# Superseal.net
KiCad netlist of a schematic drawn in Altium Designer
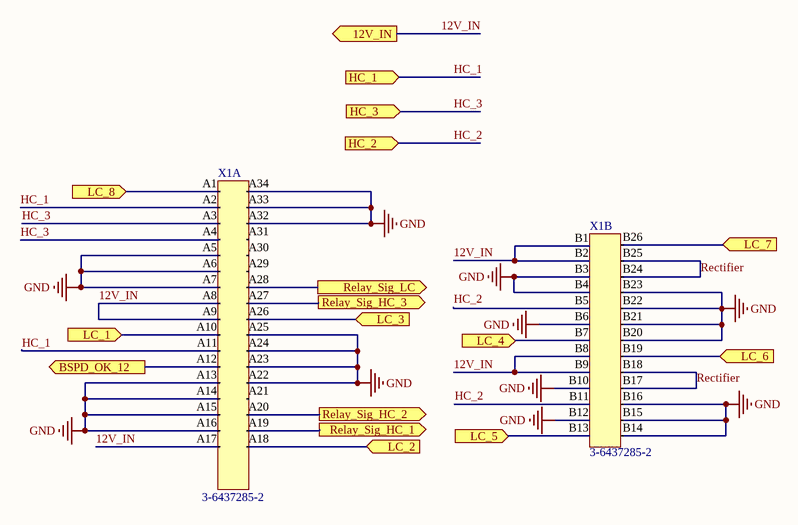
[diagram p0: Superseal.SchDoc]

(export (version "E")
  (design (tool "Eeschema 10.0.6"))
  (components
    (comp (ref "X1")
      (value "3-6437285-2")
      (footprint "SUPERSEAL 60POS 90Deg")
      (description "90 Degree")
      (libsource (lib "Altium-Lib") (part "CONN Superseal 60POS"))
    )
  )
  (nets
    (net (code "1") (name "/12V_IN") (class "Default")
      (node (ref "X1") (pin "A17") (pintype "bidirectional"))
      (node (ref "X1") (pin "A8") (pintype "bidirectional"))
      (node (ref "X1") (pin "A9") (pintype "bidirectional"))
      (node (ref "X1") (pin "B1") (pintype "bidirectional"))
      (node (ref "X1") (pin "B2") (pintype "bidirectional"))
      (node (ref "X1") (pin "B8") (pintype "bidirectional"))
      (node (ref "X1") (pin "B9") (pintype "bidirectional"))
    )
    (net (code "2") (name "/BSPD_OK_12") (class "Default")
      (node (ref "X1") (pin "A12") (pintype "bidirectional"))
    )
    (net (code "3") (name "/HC_1") (class "Default")
      (node (ref "X1") (pin "A11") (pintype "bidirectional"))
      (node (ref "X1") (pin "A2") (pintype "bidirectional"))
    )
    (net (code "4") (name "/HC_2") (class "Default")
      (node (ref "X1") (pin "B11") (pintype "bidirectional"))
      (node (ref "X1") (pin "B5") (pintype "bidirectional"))
    )
    (net (code "5") (name "/HC_3") (class "Default")
      (node (ref "X1") (pin "A3") (pintype "bidirectional"))
      (node (ref "X1") (pin "A4") (pintype "bidirectional"))
    )
    (net (code "6") (name "/LC_1") (class "Default") (node (ref "X1") (pin "A10") (pintype "bidirectional")))
    (net (code "7") (name "/LC_2") (class "Default") (node (ref "X1") (pin "A18") (pintype "bidirectional")))
    (net (code "8") (name "/LC_3") (class "Default") (node (ref "X1") (pin "A26") (pintype "bidirectional")))
    (net (code "9") (name "/LC_4") (class "Default") (node (ref "X1") (pin "B7") (pintype "bidirectional")))
    (net (code "10") (name "/LC_5") (class "Default") (node (ref "X1") (pin "B13") (pintype "bidirectional")))
    (net (code "11") (name "/LC_6") (class "Default") (node (ref "X1") (pin "B19") (pintype "bidirectional")))
    (net (code "12") (name "/LC_7") (class "Default") (node (ref "X1") (pin "B26") (pintype "bidirectional")))
    (net (code "13") (name "/LC_8") (class "Default") (node (ref "X1") (pin "A1") (pintype "bidirectional")))
    (net (code "14") (name "/Rectifier") (class "Default")
      (node (ref "X1") (pin "B17") (pintype "bidirectional"))
      (node (ref "X1") (pin "B18") (pintype "bidirectional"))
      (node (ref "X1") (pin "B24") (pintype "bidirectional"))
      (node (ref "X1") (pin "B25") (pintype "bidirectional"))
    )
    (net (code "15") (name "/Relay_Sig_HC_1") (class "Default")
      (node (ref "X1") (pin "A19") (pintype "bidirectional"))
    )
    (net (code "16") (name "/Relay_Sig_HC_2") (class "Default")
      (node (ref "X1") (pin "A20") (pintype "bidirectional"))
    )
    (net (code "17") (name "/Relay_Sig_HC_3") (class "Default")
      (node (ref "X1") (pin "A27") (pintype "bidirectional"))
    )
    (net (code "18") (name "/Relay_Sig_LC") (class "Default")
      (node (ref "X1") (pin "A28") (pintype "bidirectional"))
    )
    (net (code "19") (name "GND") (class "Default")
      (node (ref "X1") (pin "A13") (pintype "bidirectional"))
      (node (ref "X1") (pin "A14") (pintype "bidirectional"))
      (node (ref "X1") (pin "A15") (pintype "bidirectional"))
      (node (ref "X1") (pin "A16") (pintype "bidirectional"))
      (node (ref "X1") (pin "A22") (pintype "bidirectional"))
      (node (ref "X1") (pin "A23") (pintype "bidirectional"))
      (node (ref "X1") (pin "A24") (pintype "bidirectional"))
      (node (ref "X1") (pin "A25") (pintype "bidirectional"))
      (node (ref "X1") (pin "A32") (pintype "bidirectional"))
      (node (ref "X1") (pin "A33") (pintype "bidirectional"))
      (node (ref "X1") (pin "A34") (pintype "bidirectional"))
      (node (ref "X1") (pin "A5") (pintype "bidirectional"))
      (node (ref "X1") (pin "A6") (pintype "bidirectional"))
      (node (ref "X1") (pin "A7") (pintype "bidirectional"))
      (node (ref "X1") (pin "B10") (pintype "bidirectional"))
      (node (ref "X1") (pin "B12") (pintype "bidirectional"))
      (node (ref "X1") (pin "B14") (pintype "bidirectional"))
      (node (ref "X1") (pin "B15") (pintype "bidirectional"))
      (node (ref "X1") (pin "B16") (pintype "bidirectional"))
      (node (ref "X1") (pin "B20") (pintype "bidirectional"))
      (node (ref "X1") (pin "B21") (pintype "bidirectional"))
      (node (ref "X1") (pin "B22") (pintype "bidirectional"))
      (node (ref "X1") (pin "B23") (pintype "bidirectional"))
      (node (ref "X1") (pin "B3") (pintype "bidirectional"))
      (node (ref "X1") (pin "B4") (pintype "bidirectional"))
      (node (ref "X1") (pin "B6") (pintype "bidirectional"))
    )
    (net (code "20") (name "unconnected-(X1-PadA21)") (class "Default")
      (node (ref "X1") (pin "A21") (pintype "bidirectional"))
    )
    (net (code "21") (name "unconnected-(X1-PadA29)") (class "Default")
      (node (ref "X1") (pin "A29") (pintype "bidirectional"))
    )
    (net (code "22") (name "unconnected-(X1-PadA30)") (class "Default")
      (node (ref "X1") (pin "A30") (pintype "bidirectional"))
    )
    (net (code "23") (name "unconnected-(X1-PadA31)") (class "Default")
      (node (ref "X1") (pin "A31") (pintype "bidirectional"))
    )
  )
)
